# HL2SS.net
KiCad netlist of a schematic drawn in Altium Designer
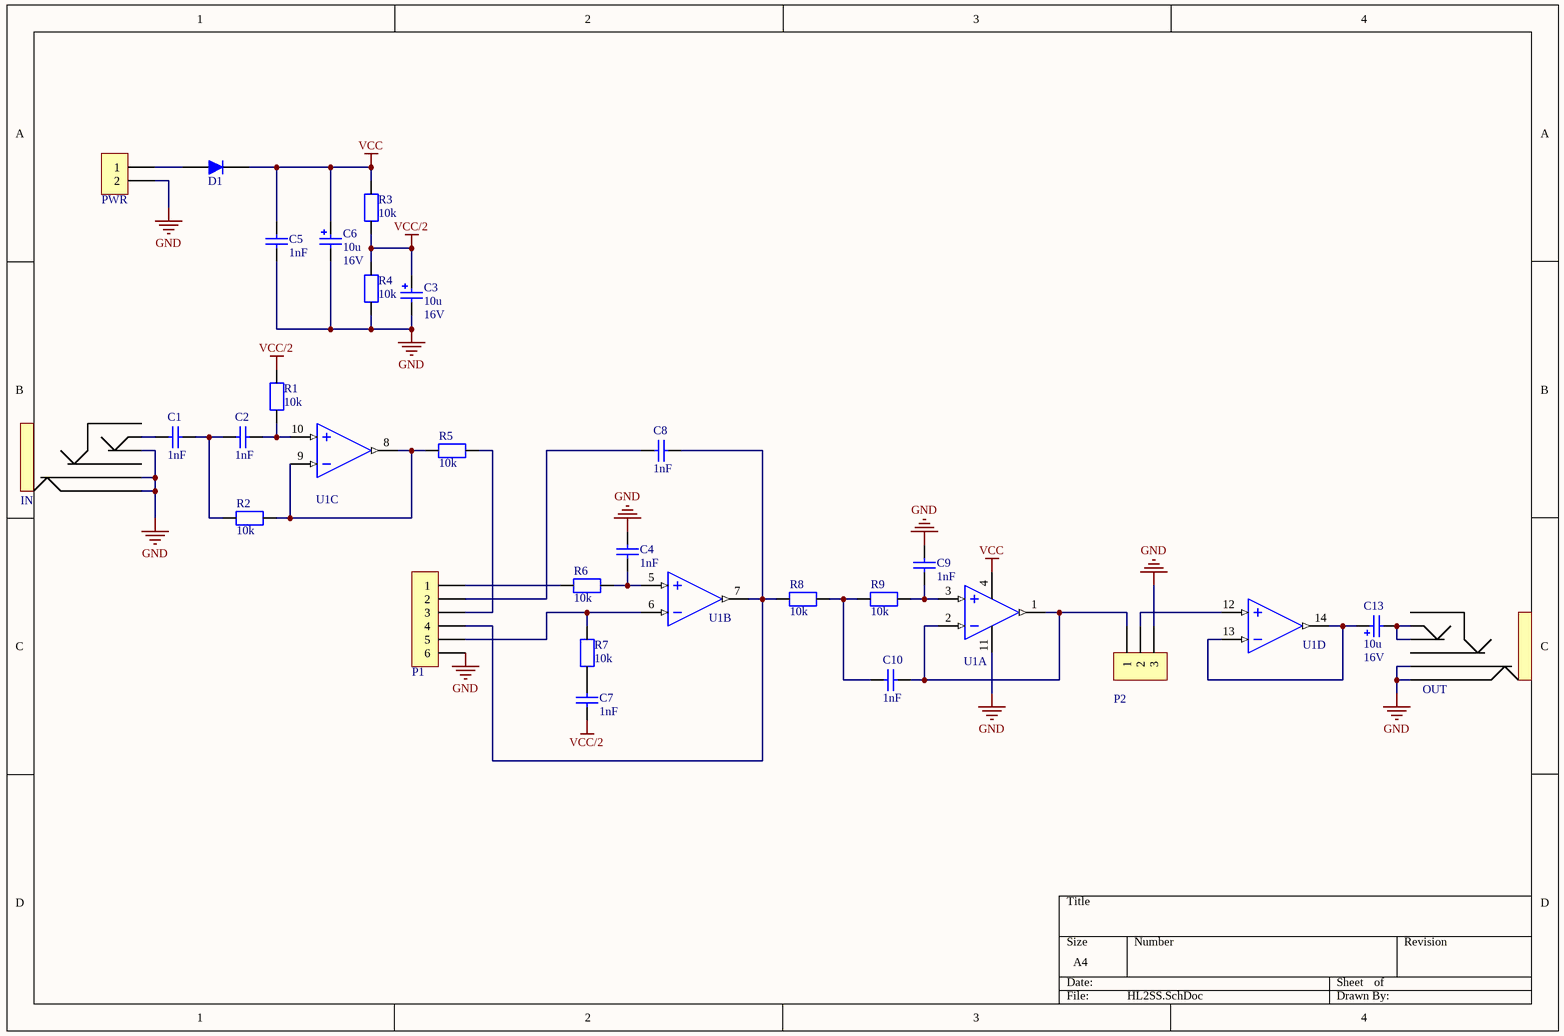
[diagram p0: HL2SS.SchDoc]

(export (version "E")
  (design (tool "Eeschema 10.0.6"))
  (components
    (comp (ref "C1")
      (value "1nF")
      (footprint "0805_Capacitor")
      (fields (field (name "Comment") "Capacitor"))
      (libsource (lib "SchLib1") (part "Capacitor"))
    )
    (comp (ref "C2")
      (value "1nF")
      (footprint "0805_Capacitor")
      (fields (field (name "Comment") "Capacitor"))
      (libsource (lib "SchLib1") (part "Capacitor"))
    )
    (comp (ref "C3")
      (value "10u")
      (footprint "ELEC_RAD10")
      (fields (field (name "INITIAL VOLTAGE") "16V") (field (name "Comment") "Electrolytic Capacitor"))
      (libsource (lib "SchLib1") (part "Electrolytic Capacitor"))
    )
    (comp (ref "C4")
      (value "1nF")
      (footprint "0805_Capacitor")
      (fields (field (name "Comment") "Capacitor"))
      (libsource (lib "SchLib1") (part "Capacitor"))
    )
    (comp (ref "C5")
      (value "1nF")
      (footprint "0805_Capacitor")
      (fields (field (name "Comment") "Capacitor"))
      (libsource (lib "SchLib1") (part "Capacitor"))
    )
    (comp (ref "C6")
      (value "10u")
      (footprint "ELEC_RAD10")
      (fields (field (name "INITIAL VOLTAGE") "16V") (field (name "Comment") "Electrolytic Capacitor"))
      (libsource (lib "SchLib1") (part "Electrolytic Capacitor"))
    )
    (comp (ref "C7")
      (value "1nF")
      (footprint "0805_Capacitor")
      (fields (field (name "Comment") "Capacitor"))
      (libsource (lib "SchLib1") (part "Capacitor"))
    )
    (comp (ref "C8")
      (value "1nF")
      (footprint "0805_Capacitor")
      (fields (field (name "Comment") "Capacitor"))
      (libsource (lib "SchLib1") (part "Capacitor"))
    )
    (comp (ref "C9")
      (value "1nF")
      (footprint "0805_Capacitor")
      (fields (field (name "Comment") "Capacitor"))
      (libsource (lib "SchLib1") (part "Capacitor"))
    )
    (comp (ref "C10")
      (value "1nF")
      (footprint "0805_Capacitor")
      (fields (field (name "Comment") "Capacitor"))
      (libsource (lib "SchLib1") (part "Capacitor"))
    )
    (comp (ref "C13")
      (value "10u")
      (footprint "ELEC_RAD10")
      (fields (field (name "INITIAL VOLTAGE") "16V") (field (name "Comment") "Electrolytic Capacitor"))
      (libsource (lib "SchLib1") (part "Electrolytic Capacitor"))
    )
    (comp (ref "D1") (value "Diode") (footprint "DO35") (libsource (lib "SchLib1") (part "Diode")))
    (comp (ref "IN") (value "Jack 6.3") (footprint "Jack 6.3") (libsource (lib "") (part "Jack 6.3_1")))
    (comp (ref "OUT") (value "Jack 6.3") (footprint "Jack 6.3") (libsource (lib "SchLib1") (part "Jack 6.3")))
    (comp (ref "P1")
      (value "SIL-CONN-6")
      (footprint "SIL-CONN-6")
      (libsource (lib "SchLib1") (part "SIL-CONN-6"))
    )
    (comp (ref "P2")
      (value "SIL-CONN-3")
      (footprint "SIL-CONN-3")
      (libsource (lib "SchLib1") (part "SIL-CONN-3"))
    )
    (comp (ref "PWR")
      (value "SIL-CONN-2")
      (footprint "SIL-CONN-2")
      (libsource (lib "SchLib1") (part "SIL-CONN-2"))
    )
    (comp (ref "R1")
      (value "10k")
      (footprint "0805_Resistor")
      (fields (field (name "Comment") "Resistor"))
      (libsource (lib "") (part "Resistor_2"))
    )
    (comp (ref "R2")
      (value "10k")
      (footprint "0805_Resistor")
      (fields (field (name "Comment") "Resistor"))
      (libsource (lib "SchLib1") (part "Resistor"))
    )
    (comp (ref "R3")
      (value "10k")
      (footprint "0805_Resistor")
      (fields (field (name "Comment") "Resistor"))
      (libsource (lib "") (part "Resistor_2"))
    )
    (comp (ref "R4")
      (value "10k")
      (footprint "0805_Resistor")
      (fields (field (name "Comment") "Resistor"))
      (libsource (lib "") (part "Resistor_2"))
    )
    (comp (ref "R5")
      (value "10k")
      (footprint "0805_Resistor")
      (fields (field (name "Comment") "Resistor"))
      (libsource (lib "SchLib1") (part "Resistor"))
    )
    (comp (ref "R6")
      (value "10k")
      (footprint "0805_Resistor")
      (fields (field (name "Comment") "Resistor"))
      (libsource (lib "SchLib1") (part "Resistor"))
    )
    (comp (ref "R7")
      (value "10k")
      (footprint "0805_Resistor")
      (fields (field (name "Comment") "Resistor"))
      (libsource (lib "") (part "Resistor_1"))
    )
    (comp (ref "R8")
      (value "10k")
      (footprint "0805_Resistor")
      (fields (field (name "Comment") "Resistor"))
      (libsource (lib "SchLib1") (part "Resistor"))
    )
    (comp (ref "R9")
      (value "10k")
      (footprint "0805_Resistor")
      (fields (field (name "Comment") "Resistor"))
      (libsource (lib "SchLib1") (part "Resistor"))
    )
    (comp (ref "U1") (value "TL074") (footprint "DIP14") (libsource (lib "SchLib1") (part "TL074")))
  )
  (nets
    (net (code "1") (name "GND") (class "Default")
      (node (ref "C3") (pin "-") (pinfunction "-_-") (pintype "passive"))
      (node (ref "C4") (pin "2") (pinfunction "2_2") (pintype "passive"))
      (node (ref "C5") (pin "1") (pinfunction "1_1") (pintype "passive"))
      (node (ref "C6") (pin "-") (pinfunction "-_-") (pintype "passive"))
      (node (ref "C9") (pin "2") (pinfunction "2_2") (pintype "passive"))
      (node (ref "IN") (pin "2") (pinfunction "2_2") (pintype "passive"))
      (node (ref "IN") (pin "3") (pinfunction "3_3") (pintype "passive"))
      (node (ref "IN") (pin "4") (pinfunction "4_4") (pintype "passive"))
      (node (ref "OUT") (pin "3") (pinfunction "3_3") (pintype "passive"))
      (node (ref "OUT") (pin "4") (pinfunction "4_4") (pintype "passive"))
      (node (ref "P1") (pin "6") (pinfunction "6_6") (pintype "passive"))
      (node (ref "P2") (pin "3") (pinfunction "3_3") (pintype "passive"))
      (node (ref "PWR") (pin "2") (pinfunction "2_2") (pintype "passive"))
      (node (ref "R4") (pin "1") (pinfunction "1_1") (pintype "passive"))
      (node (ref "U1") (pin "11") (pinfunction "11_11") (pintype "power_in"))
    )
    (net (code "2") (name "Net-(C1-Pad1)") (class "Default")
      (node (ref "C1") (pin "1") (pinfunction "1_1") (pintype "passive"))
      (node (ref "IN") (pin "1") (pinfunction "1_1") (pintype "passive"))
    )
    (net (code "3") (name "Net-(C1-Pad2)") (class "Default")
      (node (ref "C1") (pin "2") (pinfunction "2_2") (pintype "passive"))
      (node (ref "C2") (pin "1") (pinfunction "1_1") (pintype "passive"))
      (node (ref "R2") (pin "1") (pinfunction "1_1") (pintype "passive"))
    )
    (net (code "4") (name "Net-(C7-Pad2)") (class "Default")
      (node (ref "C7") (pin "2") (pinfunction "2_2") (pintype "passive"))
      (node (ref "R7") (pin "2") (pinfunction "2_2") (pintype "passive"))
    )
    (net (code "5") (name "Net-(C8-Pad1)") (class "Default")
      (node (ref "C8") (pin "1") (pinfunction "1_1") (pintype "passive"))
      (node (ref "P1") (pin "2") (pinfunction "2_2") (pintype "passive"))
    )
    (net (code "6") (name "Net-(C10-Pad1)") (class "Default")
      (node (ref "C10") (pin "1") (pinfunction "1_1") (pintype "passive"))
      (node (ref "R8") (pin "2") (pinfunction "2_2") (pintype "passive"))
      (node (ref "R9") (pin "1") (pinfunction "1_1") (pintype "passive"))
    )
    (net (code "7") (name "Net-(C13-Pad-)") (class "Default")
      (node (ref "C13") (pin "-") (pinfunction "-_-") (pintype "passive"))
      (node (ref "OUT") (pin "1") (pinfunction "1_1") (pintype "passive"))
      (node (ref "OUT") (pin "2") (pinfunction "2_2") (pintype "passive"))
    )
    (net (code "8") (name "Net-(D1-PadA)") (class "Default")
      (node (ref "D1") (pin "A") (pinfunction "A_A") (pintype "passive"))
      (node (ref "PWR") (pin "1") (pinfunction "1_1") (pintype "passive"))
    )
    (net (code "9") (name "Net-(P1-Pad1)") (class "Default")
      (node (ref "P1") (pin "1") (pinfunction "1_1") (pintype "passive"))
      (node (ref "R6") (pin "1") (pinfunction "1_1") (pintype "passive"))
    )
    (net (code "10") (name "Net-(P1-Pad3)") (class "Default")
      (node (ref "P1") (pin "3") (pinfunction "3_3") (pintype "passive"))
      (node (ref "R5") (pin "2") (pinfunction "2_2") (pintype "passive"))
    )
    (net (code "11") (name "Net-(U1A-+)") (class "Default")
      (node (ref "C9") (pin "1") (pinfunction "1_1") (pintype "passive"))
      (node (ref "R9") (pin "2") (pinfunction "2_2") (pintype "passive"))
      (node (ref "U1") (pin "3") (pinfunction "+_3") (pintype "input"))
    )
    (net (code "12") (name "Net-(U1A--)") (class "Default")
      (node (ref "C10") (pin "2") (pinfunction "2_2") (pintype "passive"))
      (node (ref "P2") (pin "1") (pinfunction "1_1") (pintype "passive"))
      (node (ref "U1") (pin "1") (pinfunction "O_1") (pintype "output"))
      (node (ref "U1") (pin "2") (pinfunction "-_2") (pintype "input"))
    )
    (net (code "13") (name "Net-(U1B-+)") (class "Default")
      (node (ref "C4") (pin "1") (pinfunction "1_1") (pintype "passive"))
      (node (ref "R6") (pin "2") (pinfunction "2_2") (pintype "passive"))
      (node (ref "U1") (pin "5") (pinfunction "+_5") (pintype "input"))
    )
    (net (code "14") (name "Net-(U1B--)") (class "Default")
      (node (ref "P1") (pin "5") (pinfunction "5_5") (pintype "passive"))
      (node (ref "R7") (pin "1") (pinfunction "1_1") (pintype "passive"))
      (node (ref "U1") (pin "6") (pinfunction "-_6") (pintype "input"))
    )
    (net (code "15") (name "Net-(U1B-O)") (class "Default")
      (node (ref "C8") (pin "2") (pinfunction "2_2") (pintype "passive"))
      (node (ref "P1") (pin "4") (pinfunction "4_4") (pintype "passive"))
      (node (ref "R8") (pin "1") (pinfunction "1_1") (pintype "passive"))
      (node (ref "U1") (pin "7") (pinfunction "O_7") (pintype "output"))
    )
    (net (code "16") (name "Net-(U1C-+)") (class "Default")
      (node (ref "C2") (pin "2") (pinfunction "2_2") (pintype "passive"))
      (node (ref "R1") (pin "1") (pinfunction "1_1") (pintype "passive"))
      (node (ref "U1") (pin "10") (pinfunction "+_10") (pintype "input"))
    )
    (net (code "17") (name "Net-(U1C--)") (class "Default")
      (node (ref "R2") (pin "2") (pinfunction "2_2") (pintype "passive"))
      (node (ref "R5") (pin "1") (pinfunction "1_1") (pintype "passive"))
      (node (ref "U1") (pin "8") (pinfunction "O_8") (pintype "output"))
      (node (ref "U1") (pin "9") (pinfunction "-_9") (pintype "input"))
    )
    (net (code "18") (name "Net-(U1D-+)") (class "Default")
      (node (ref "P2") (pin "2") (pinfunction "2_2") (pintype "passive"))
      (node (ref "U1") (pin "12") (pinfunction "+_12") (pintype "input"))
    )
    (net (code "19") (name "Net-(U1D--)") (class "Default")
      (node (ref "C13") (pin "+") (pinfunction "+_+") (pintype "passive"))
      (node (ref "U1") (pin "13") (pinfunction "-_13") (pintype "input"))
      (node (ref "U1") (pin "14") (pinfunction "O_14") (pintype "output"))
    )
    (net (code "20") (name "VCC") (class "Default")
      (node (ref "C5") (pin "2") (pinfunction "2_2") (pintype "passive"))
      (node (ref "C6") (pin "+") (pinfunction "+_+") (pintype "passive"))
      (node (ref "D1") (pin "K") (pinfunction "K_K") (pintype "passive"))
      (node (ref "R3") (pin "2") (pinfunction "2_2") (pintype "passive"))
      (node (ref "U1") (pin "4") (pinfunction "4_4") (pintype "power_in"))
    )
    (net (code "21") (name "VCC{slash}2") (class "Default")
      (node (ref "C3") (pin "+") (pinfunction "+_+") (pintype "passive"))
      (node (ref "C7") (pin "1") (pinfunction "1_1") (pintype "passive"))
      (node (ref "R1") (pin "2") (pinfunction "2_2") (pintype "passive"))
      (node (ref "R3") (pin "1") (pinfunction "1_1") (pintype "passive"))
      (node (ref "R4") (pin "2") (pinfunction "2_2") (pintype "passive"))
    )
    (net (code "22") (name "unconnected-(IN-Pad5)") (class "Default")
      (node (ref "IN") (pin "5") (pinfunction "5_5") (pintype "passive"))
    )
    (net (code "23") (name "unconnected-(IN-Pad6)") (class "Default")
      (node (ref "IN") (pin "6") (pinfunction "6_6") (pintype "passive"))
    )
    (net (code "24") (name "unconnected-(OUT-Pad5)") (class "Default")
      (node (ref "OUT") (pin "5") (pinfunction "5_5") (pintype "passive"))
    )
    (net (code "25") (name "unconnected-(OUT-Pad6)") (class "Default")
      (node (ref "OUT") (pin "6") (pinfunction "6_6") (pintype "passive"))
    )
  )
)
